# ConectoresSalida.net
KiCad netlist of a schematic drawn in Altium Designer
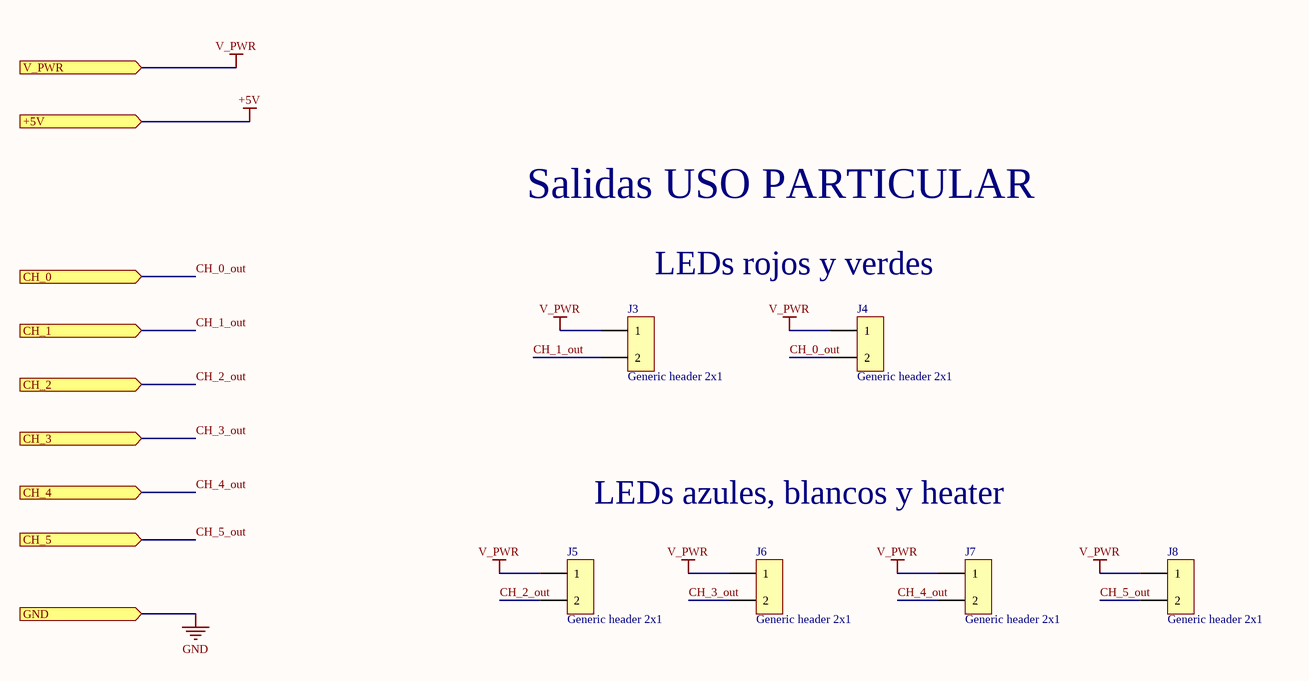
[diagram p0: ConectoresSalida.SchDoc]

(export (version "E")
  (design (tool "Eeschema 10.0.6"))
  (components
    (comp (ref "J3")
      (value "Generic header 2x1")
      (footprint "JST-2x1")
      (description "Generic Header 2pos, 1 row, 2.54 pitch")
      (fields
        (field (name "MANUFACTURER") "CJT(Changjiang Connectors)")
        (field (name "MANUFACTURER PART NUMBER") "A2547WV-2P")
      )
      (libsource (lib "IoWLabsConnectors") (part "Header - 2x1"))
    )
    (comp (ref "J4")
      (value "Generic header 2x1")
      (footprint "JST-2x1")
      (description "Generic Header 2pos, 1 row, 2.54 pitch")
      (fields
        (field (name "MANUFACTURER") "CJT(Changjiang Connectors)")
        (field (name "MANUFACTURER PART NUMBER") "A2547WV-2P")
      )
      (libsource (lib "IoWLabsConnectors") (part "Header - 2x1"))
    )
    (comp (ref "J5")
      (value "Generic header 2x1")
      (footprint "JST-2x1")
      (description "Generic Header 2pos, 1 row, 2.54 pitch")
      (fields
        (field (name "MANUFACTURER") "CJT(Changjiang Connectors)")
        (field (name "MANUFACTURER PART NUMBER") "A2547WV-2P")
      )
      (libsource (lib "IoWLabsConnectors") (part "Header - 2x1"))
    )
    (comp (ref "J6")
      (value "Generic header 2x1")
      (footprint "JST-2x1")
      (description "Generic Header 2pos, 1 row, 2.54 pitch")
      (fields
        (field (name "MANUFACTURER") "CJT(Changjiang Connectors)")
        (field (name "MANUFACTURER PART NUMBER") "A2547WV-2P")
      )
      (libsource (lib "IoWLabsConnectors") (part "Header - 2x1"))
    )
    (comp (ref "J7")
      (value "Generic header 2x1")
      (footprint "JST-2x1")
      (description "Generic Header 2pos, 1 row, 2.54 pitch")
      (fields
        (field (name "MANUFACTURER") "CJT(Changjiang Connectors)")
        (field (name "MANUFACTURER PART NUMBER") "A2547WV-2P")
      )
      (libsource (lib "IoWLabsConnectors") (part "Header - 2x1"))
    )
    (comp (ref "J8")
      (value "Generic header 2x1")
      (footprint "JST-2x1")
      (description "Generic Header 2pos, 1 row, 2.54 pitch")
      (fields
        (field (name "MANUFACTURER") "CJT(Changjiang Connectors)")
        (field (name "MANUFACTURER PART NUMBER") "A2547WV-2P")
      )
      (libsource (lib "IoWLabsConnectors") (part "Header - 2x1"))
    )
  )
  (nets
    (net (code "2") (name "/CH_0_out") (class "Default")
      (node (ref "J4") (pin "2") (pinfunction "2_2") (pintype "passive"))
    )
    (net (code "3") (name "/CH_1_out") (class "Default")
      (node (ref "J3") (pin "2") (pinfunction "2_2") (pintype "passive"))
    )
    (net (code "4") (name "/CH_2_out") (class "Default")
      (node (ref "J5") (pin "2") (pinfunction "2_2") (pintype "passive"))
    )
    (net (code "5") (name "/CH_3_out") (class "Default")
      (node (ref "J6") (pin "2") (pinfunction "2_2") (pintype "passive"))
    )
    (net (code "6") (name "/CH_4_out") (class "Default")
      (node (ref "J7") (pin "2") (pinfunction "2_2") (pintype "passive"))
    )
    (net (code "7") (name "/CH_5_out") (class "Default")
      (node (ref "J8") (pin "2") (pinfunction "2_2") (pintype "passive"))
    )
    (net (code "9") (name "V_PWR") (class "Default")
      (node (ref "J3") (pin "1") (pinfunction "1_1") (pintype "passive"))
      (node (ref "J4") (pin "1") (pinfunction "1_1") (pintype "passive"))
      (node (ref "J5") (pin "1") (pinfunction "1_1") (pintype "passive"))
      (node (ref "J6") (pin "1") (pinfunction "1_1") (pintype "passive"))
      (node (ref "J7") (pin "1") (pinfunction "1_1") (pintype "passive"))
      (node (ref "J8") (pin "1") (pinfunction "1_1") (pintype "passive"))
    )
  )
)
